# MCU.net
KiCad netlist of a schematic drawn in Altium Designer
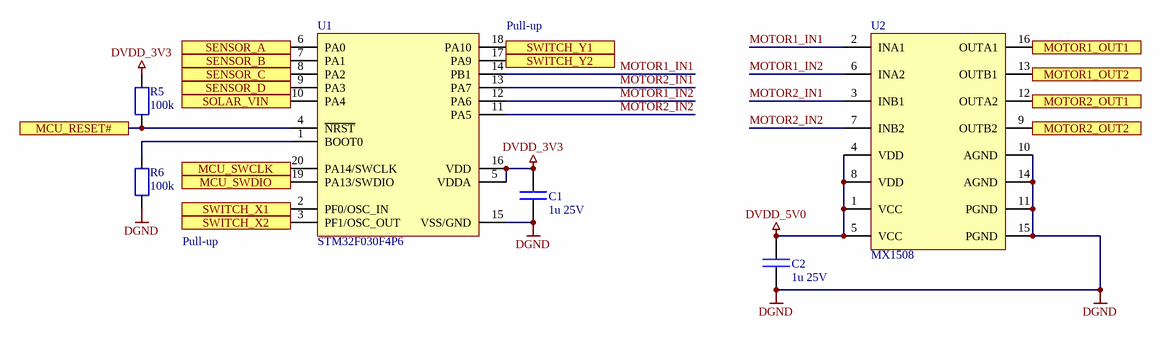
[diagram p0: MCU.SchDoc]

(export (version "E")
  (design (tool "Eeschema 10.0.6"))
  (components
    (comp (ref "C1")
      (value "1u 25V")
      (footprint "C_0603/1608")
      (description "Non-polarized capacitor")
      (libsource (lib "passive") (part "Capacitor"))
    )
    (comp (ref "C2")
      (value "1u 25V")
      (footprint "C_0603/1608")
      (description "Non-polarized capacitor")
      (libsource (lib "passive") (part "Capacitor"))
    )
    (comp (ref "R5")
      (value "100k")
      (footprint "R_0603/1608")
      (description "Resistor")
      (libsource (lib "passive") (part "Resistor"))
    )
    (comp (ref "R6")
      (value "100k")
      (footprint "R_0603/1608")
      (description "Resistor")
      (libsource (lib "passive") (part "Resistor"))
    )
    (comp (ref "U1")
      (value "STM32F030F4P6")
      (footprint "SO20_0.65")
      (description "32-bit Cortex-M0")
      (libsource (lib "MCU and memory") (part "STM32F030F"))
    )
    (comp (ref "U2")
      (value "MX1508")
      (footprint "SO16_1.27")
      (description "Dual DC motor driver")
      (libsource (lib "power") (part "MX1508"))
    )
  )
  (nets
    (net (code "1") (name "/MCU_RESET#") (class "Default")
      (node (ref "R5") (pin "2") (pintype "passive"))
      (node (ref "U1") (pin "4") (pinfunction "~{NRST}_4") (pintype "passive"))
    )
    (net (code "2") (name "/MCU_SWCLK") (class "Default")
      (node (ref "U1") (pin "20") (pinfunction "PA14/SWCLK_20") (pintype "passive"))
    )
    (net (code "3") (name "/MCU_SWDIO") (class "Default")
      (node (ref "U1") (pin "19") (pinfunction "PA13/SWDIO_19") (pintype "passive"))
    )
    (net (code "4") (name "/MOTOR1_IN1") (class "Default")
      (node (ref "U1") (pin "14") (pinfunction "PB1_14") (pintype "passive"))
      (node (ref "U2") (pin "2") (pinfunction "INA1_2") (pintype "passive"))
    )
    (net (code "5") (name "/MOTOR1_IN2") (class "Default")
      (node (ref "U1") (pin "12") (pinfunction "PA6_12") (pintype "passive"))
      (node (ref "U2") (pin "6") (pinfunction "INA2_6") (pintype "passive"))
    )
    (net (code "6") (name "/MOTOR1_OUT1") (class "Default")
      (node (ref "U2") (pin "16") (pinfunction "OUTA1_16") (pintype "passive"))
    )
    (net (code "7") (name "/MOTOR1_OUT2") (class "Default")
      (node (ref "U2") (pin "13") (pinfunction "OUTB1_13") (pintype "passive"))
    )
    (net (code "8") (name "/MOTOR2_IN1") (class "Default")
      (node (ref "U1") (pin "13") (pinfunction "PA7_13") (pintype "passive"))
      (node (ref "U2") (pin "3") (pinfunction "INB1_3") (pintype "passive"))
    )
    (net (code "9") (name "/MOTOR2_IN2") (class "Default")
      (node (ref "U1") (pin "11") (pinfunction "PA5_11") (pintype "passive"))
      (node (ref "U2") (pin "7") (pinfunction "INB2_7") (pintype "passive"))
    )
    (net (code "10") (name "/MOTOR2_OUT1") (class "Default")
      (node (ref "U2") (pin "12") (pinfunction "OUTA2_12") (pintype "passive"))
    )
    (net (code "11") (name "/MOTOR2_OUT2") (class "Default")
      (node (ref "U2") (pin "9") (pinfunction "OUTB2_9") (pintype "passive"))
    )
    (net (code "12") (name "/SENSOR_A") (class "Default")
      (node (ref "U1") (pin "6") (pinfunction "PA0_6") (pintype "passive"))
    )
    (net (code "13") (name "/SENSOR_B") (class "Default")
      (node (ref "U1") (pin "7") (pinfunction "PA1_7") (pintype "passive"))
    )
    (net (code "14") (name "/SENSOR_C") (class "Default")
      (node (ref "U1") (pin "8") (pinfunction "PA2_8") (pintype "passive"))
    )
    (net (code "15") (name "/SENSOR_D") (class "Default")
      (node (ref "U1") (pin "9") (pinfunction "PA3_9") (pintype "passive"))
    )
    (net (code "16") (name "/SOLAR_VIN") (class "Default")
      (node (ref "U1") (pin "10") (pinfunction "PA4_10") (pintype "passive"))
    )
    (net (code "17") (name "/SWITCH_X1") (class "Default")
      (node (ref "U1") (pin "2") (pinfunction "PF0/OSC_IN_2") (pintype "passive"))
    )
    (net (code "18") (name "/SWITCH_X2") (class "Default")
      (node (ref "U1") (pin "3") (pinfunction "PF1/OSC_OUT_3") (pintype "passive"))
    )
    (net (code "19") (name "/SWITCH_Y1") (class "Default")
      (node (ref "U1") (pin "18") (pinfunction "PA10_18") (pintype "passive"))
    )
    (net (code "20") (name "/SWITCH_Y2") (class "Default")
      (node (ref "U1") (pin "17") (pinfunction "PA9_17") (pintype "passive"))
    )
    (net (code "21") (name "DGND") (class "Default")
      (node (ref "C1") (pin "2") (pintype "passive"))
      (node (ref "C2") (pin "2") (pintype "passive"))
      (node (ref "R6") (pin "1") (pintype "passive"))
      (node (ref "U1") (pin "15") (pinfunction "VSS/GND_15") (pintype "passive"))
      (node (ref "U2") (pin "10") (pinfunction "AGND_10") (pintype "passive"))
      (node (ref "U2") (pin "11") (pinfunction "PGND_11") (pintype "passive"))
      (node (ref "U2") (pin "14") (pinfunction "AGND_14") (pintype "passive"))
      (node (ref "U2") (pin "15") (pinfunction "PGND_15") (pintype "passive"))
    )
    (net (code "22") (name "DVDD_3V3") (class "Default")
      (node (ref "C1") (pin "1") (pintype "passive"))
      (node (ref "R5") (pin "1") (pintype "passive"))
      (node (ref "U1") (pin "16") (pinfunction "VDD_16") (pintype "passive"))
      (node (ref "U1") (pin "5") (pinfunction "VDDA_5") (pintype "passive"))
    )
    (net (code "23") (name "DVDD_5V0") (class "Default")
      (node (ref "C2") (pin "1") (pintype "passive"))
      (node (ref "U2") (pin "1") (pinfunction "VCC_1") (pintype "passive"))
      (node (ref "U2") (pin "4") (pinfunction "VDD_4") (pintype "passive"))
      (node (ref "U2") (pin "5") (pinfunction "VCC_5") (pintype "passive"))
      (node (ref "U2") (pin "8") (pinfunction "VDD_8") (pintype "passive"))
    )
    (net (code "24") (name "Net-(U1-BOOT0)") (class "Default")
      (node (ref "R6") (pin "2") (pintype "passive"))
      (node (ref "U1") (pin "1") (pinfunction "BOOT0_1") (pintype "passive"))
    )
    (net (code "25") (name "unconnected-(U1-EP-Pad0)") (class "Default")
      (node (ref "U1") (pin "0") (pinfunction "EP_0") (pintype "passive"))
    )
  )
)
